# current_controller.net
KiCad netlist of a schematic drawn in EAGLE
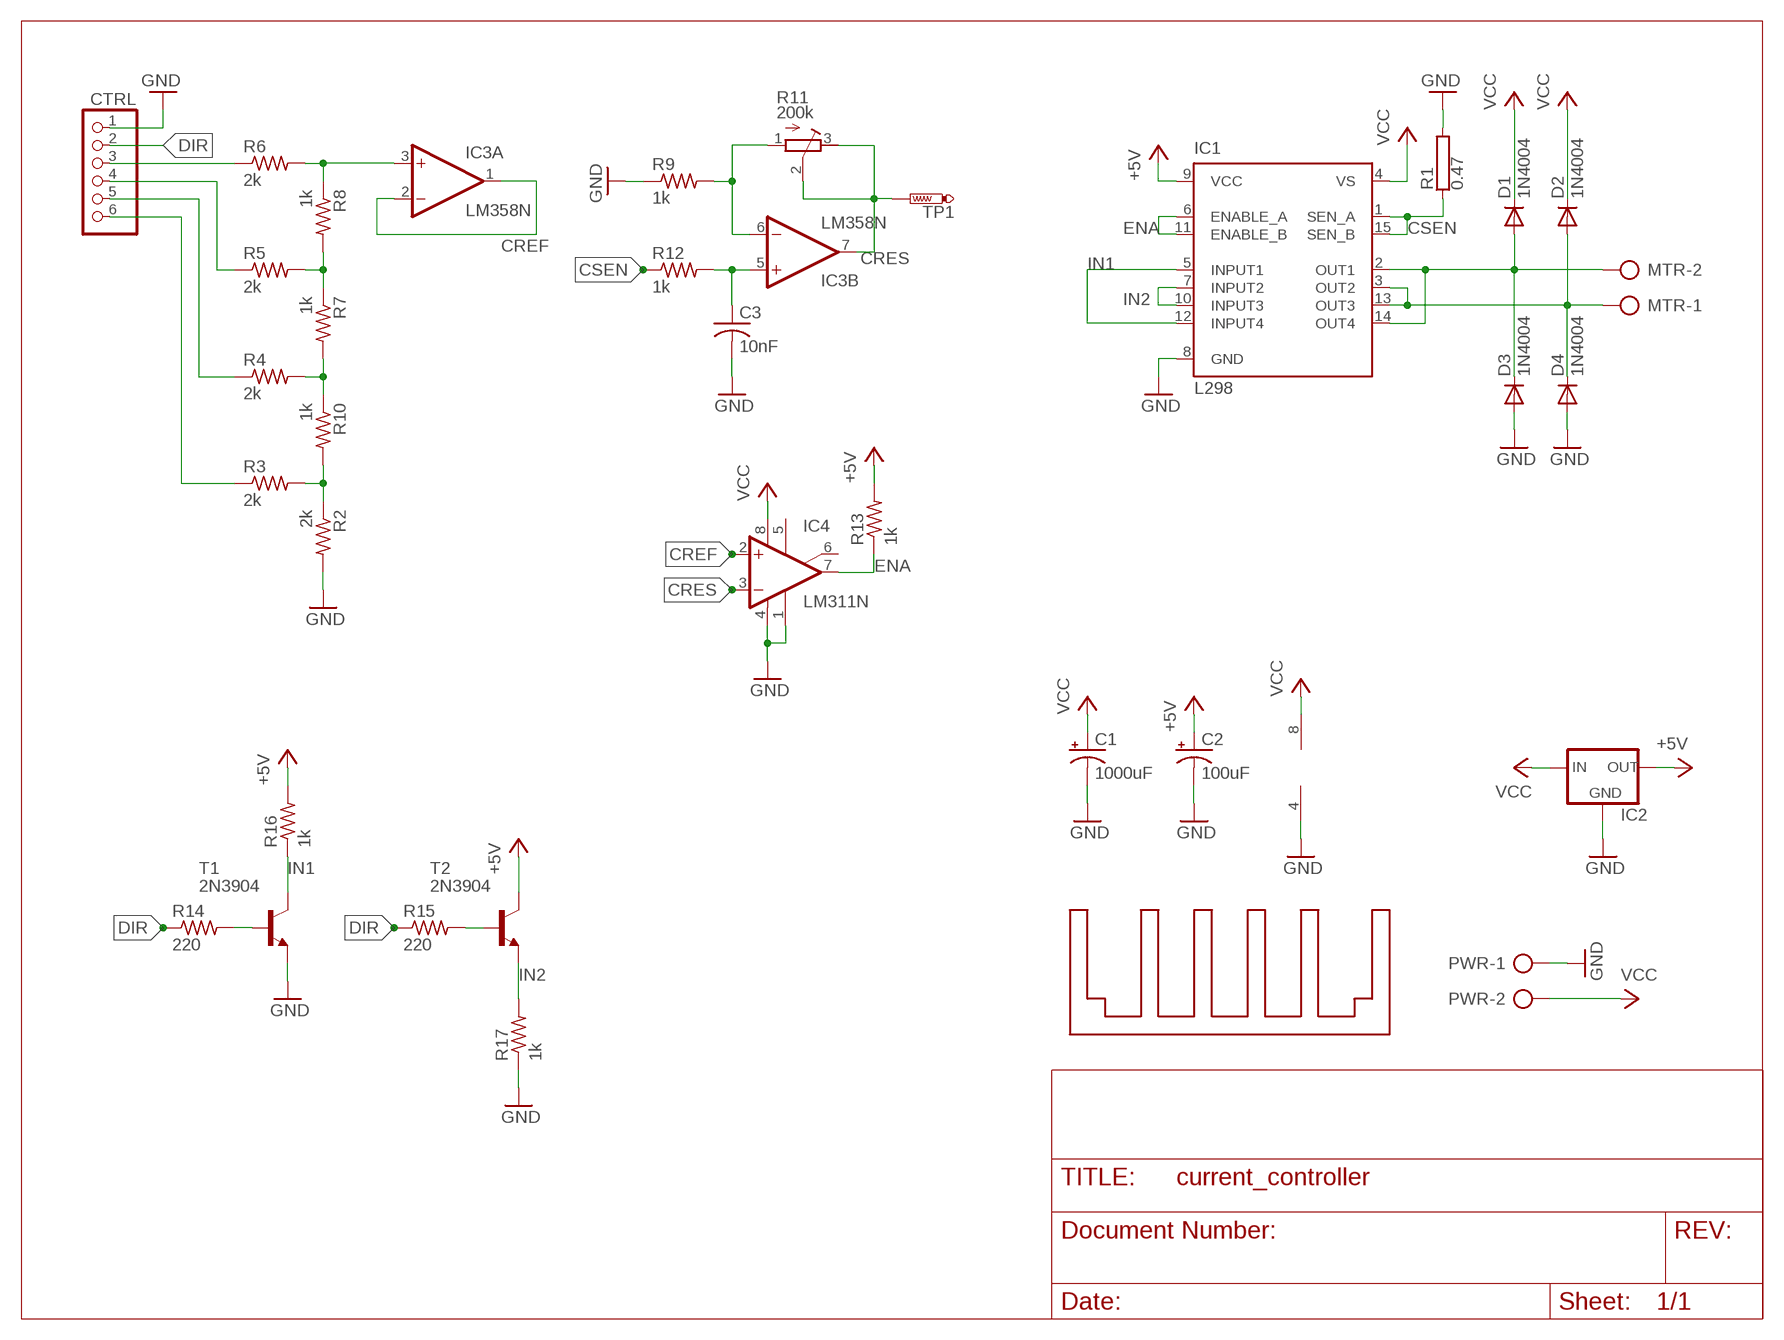
[diagram p0: schematic, sheet 1]

(export (version "E")
  (design (tool "Eeschema 10.0.6"))
  (components
    (comp (ref "C1")
      (value "1000uF")
      (footprint "eagle-import:E5-13")
      (libsource (lib "eagle-import") (part "CPOL-USE5-13"))
    )
    (comp (ref "C2")
      (value "100uF")
      (footprint "eagle-import:E5-8,5")
      (libsource (lib "eagle-import") (part "CPOL-USE5-8.5"))
    )
    (comp (ref "C3")
      (value "10nF")
      (footprint "eagle-import:C050-024X044")
      (libsource (lib "eagle-import") (part "C-US050-024X044"))
    )
    (comp (ref "CTRL")
      (value "PINHD-1X6")
      (footprint "eagle-import:1X06")
      (libsource (lib "eagle-import") (part "PINHD-1X6"))
    )
    (comp (ref "D1")
      (value "1N4004")
      (footprint "eagle-import:DO41-10")
      (libsource (lib "eagle-import") (part "1N4004"))
    )
    (comp (ref "D2")
      (value "1N4004")
      (footprint "eagle-import:DO41-10")
      (libsource (lib "eagle-import") (part "1N4004"))
    )
    (comp (ref "D3")
      (value "1N4004")
      (footprint "eagle-import:DO41-10")
      (libsource (lib "eagle-import") (part "1N4004"))
    )
    (comp (ref "D4")
      (value "1N4004")
      (footprint "eagle-import:DO41-10")
      (libsource (lib "eagle-import") (part "1N4004"))
    )
    (comp (ref "IC1")
      (value "L298")
      (footprint "eagle-import:MULTIWATT-15")
      (fields (field (name "MPN") "L298N"))
      (libsource (lib "eagle-import") (part "L298"))
    )
    (comp (ref "IC2")
      (value "78XXS")
      (footprint "eagle-import:78XXS")
      (libsource (lib "eagle-import") (part "78XXS"))
    )
    (comp (ref "IC3")
      (value "LM358N")
      (footprint "eagle-import:DIL08")
      (libsource (lib "eagle-import") (part "LM358N"))
    )
    (comp (ref "IC4")
      (value "LM311N")
      (footprint "eagle-import:DIL08")
      (libsource (lib "eagle-import") (part "LM311N"))
    )
    (comp (ref "MTR")
      (value "AK500/2")
      (footprint "eagle-import:AK500_2")
      (libsource (lib "eagle-import") (part "AK500/2"))
    )
    (comp (ref "PWR")
      (value "AK500/2")
      (footprint "eagle-import:AK500_2")
      (libsource (lib "eagle-import") (part "AK500/2"))
    )
    (comp (ref "R1")
      (value "0.47")
      (footprint "eagle-import:CA4080")
      (libsource (lib "eagle-import") (part "RCA4080"))
    )
    (comp (ref "R2")
      (value "2k")
      (footprint "eagle-import:0204_7")
      (libsource (lib "eagle-import") (part "R-US_0204/7"))
    )
    (comp (ref "R3")
      (value "2k")
      (footprint "eagle-import:0204_7")
      (libsource (lib "eagle-import") (part "R-US_0204/7"))
    )
    (comp (ref "R4")
      (value "2k")
      (footprint "eagle-import:0204_7")
      (libsource (lib "eagle-import") (part "R-US_0204/7"))
    )
    (comp (ref "R5")
      (value "2k")
      (footprint "eagle-import:0204_7")
      (libsource (lib "eagle-import") (part "R-US_0204/7"))
    )
    (comp (ref "R6")
      (value "2k")
      (footprint "eagle-import:0204_7")
      (libsource (lib "eagle-import") (part "R-US_0204/7"))
    )
    (comp (ref "R7")
      (value "1k")
      (footprint "eagle-import:0204_7")
      (libsource (lib "eagle-import") (part "R-US_0204/7"))
    )
    (comp (ref "R8")
      (value "1k")
      (footprint "eagle-import:0204_7")
      (libsource (lib "eagle-import") (part "R-US_0204/7"))
    )
    (comp (ref "R9")
      (value "1k")
      (footprint "eagle-import:0204_7")
      (libsource (lib "eagle-import") (part "R-US_0204/7"))
    )
    (comp (ref "R10")
      (value "1k")
      (footprint "eagle-import:0204_7")
      (libsource (lib "eagle-import") (part "R-US_0204/7"))
    )
    (comp (ref "R11")
      (value "200k")
      (footprint "eagle-import:RTRIM64W")
      (libsource (lib "eagle-import") (part "R-TRIMM64W"))
    )
    (comp (ref "R12")
      (value "1k")
      (footprint "eagle-import:0204_7")
      (libsource (lib "eagle-import") (part "R-US_0204/7"))
    )
    (comp (ref "R13")
      (value "1k")
      (footprint "eagle-import:0204_7")
      (libsource (lib "eagle-import") (part "R-US_0204/7"))
    )
    (comp (ref "R14")
      (value "220")
      (footprint "eagle-import:0204_7")
      (libsource (lib "eagle-import") (part "R-US_0204/7"))
    )
    (comp (ref "R15")
      (value "220")
      (footprint "eagle-import:0204_7")
      (libsource (lib "eagle-import") (part "R-US_0204/7"))
    )
    (comp (ref "R16")
      (value "1k")
      (footprint "eagle-import:0204_7")
      (libsource (lib "eagle-import") (part "R-US_0204/7"))
    )
    (comp (ref "R17")
      (value "1k")
      (footprint "eagle-import:0204_7")
      (libsource (lib "eagle-import") (part "R-US_0204/7"))
    )
    (comp (ref "T1")
      (value "2N3904")
      (footprint "eagle-import:TO92")
      (libsource (lib "eagle-import") (part "2N3904"))
    )
    (comp (ref "T2")
      (value "2N3904")
      (footprint "eagle-import:TO92")
      (libsource (lib "eagle-import") (part "2N3904"))
    )
    (comp (ref "TP1")
      (value "PTR1PAD1-13Y")
      (footprint "eagle-import:P1-13Y")
      (libsource (lib "eagle-import") (part "PTR1PAD1-13Y"))
    )
    (comp (ref "U$1")
      (value "MULTI15_HEATSINK")
      (footprint "eagle-import:MULTI15_HEATSINK")
      (libsource (lib "eagle-import") (part "MULTI15_HEATSINK"))
    )
  )
  (nets
    (net (code "1") (name "+5V") (class "Default")
      (node (ref "C2") (pin "+") (pinfunction "+_+") (pintype "passive"))
      (node (ref "IC1") (pin "9") (pinfunction "VCC_9") (pintype "power_in"))
      (node (ref "IC2") (pin "OUT") (pinfunction "OUT_OUT") (pintype "passive"))
      (node (ref "R13") (pin "2") (pinfunction "2_2") (pintype "passive"))
      (node (ref "R16") (pin "2") (pinfunction "2_2") (pintype "passive"))
      (node (ref "T2") (pin "1") (pinfunction "C_1") (pintype "passive"))
    )
    (net (code "2") (name "/ENA") (class "Default")
      (node (ref "IC1") (pin "11") (pinfunction "ENABLE_B_11") (pintype "input"))
      (node (ref "IC1") (pin "6") (pinfunction "ENABLE_A_6") (pintype "input"))
      (node (ref "IC4") (pin "7") (pinfunction "OUT_7") (pintype "output"))
      (node (ref "R13") (pin "1") (pinfunction "1_1") (pintype "passive"))
    )
    (net (code "3") (name "/IN1") (class "Default")
      (node (ref "IC1") (pin "12") (pinfunction "INPUT4_12") (pintype "input"))
      (node (ref "IC1") (pin "5") (pinfunction "INPUT1_5") (pintype "input"))
      (node (ref "R16") (pin "1") (pinfunction "1_1") (pintype "passive"))
      (node (ref "T1") (pin "1") (pinfunction "C_1") (pintype "passive"))
    )
    (net (code "4") (name "/IN2") (class "Default")
      (node (ref "IC1") (pin "10") (pinfunction "INPUT3_10") (pintype "input"))
      (node (ref "IC1") (pin "7") (pinfunction "INPUT2_7") (pintype "input"))
      (node (ref "R17") (pin "2") (pinfunction "2_2") (pintype "passive"))
      (node (ref "T2") (pin "3") (pinfunction "E_3") (pintype "passive"))
    )
    (net (code "5") (name "CREF") (class "Default")
      (node (ref "IC3") (pin "1") (pinfunction "OUT_1") (pintype "output"))
      (node (ref "IC3") (pin "2") (pinfunction "-IN_2") (pintype "input"))
      (node (ref "IC4") (pin "2") (pinfunction "+IN_2") (pintype "input"))
    )
    (net (code "6") (name "CRES") (class "Default")
      (node (ref "IC3") (pin "7") (pinfunction "OUT_7") (pintype "output"))
      (node (ref "IC4") (pin "3") (pinfunction "-IN_3") (pintype "input"))
      (node (ref "R11") (pin "2") (pinfunction "S_2") (pintype "passive"))
      (node (ref "R11") (pin "3") (pinfunction "E_3") (pintype "passive"))
      (node (ref "TP1") (pin "TP") (pinfunction "TP_TP") (pintype "input"))
    )
    (net (code "7") (name "CSEN") (class "Default")
      (node (ref "IC1") (pin "1") (pinfunction "SEN_A_1") (pintype "input"))
      (node (ref "IC1") (pin "15") (pinfunction "SEN_B_15") (pintype "input"))
      (node (ref "R1") (pin "1") (pinfunction "1_1") (pintype "passive"))
      (node (ref "R12") (pin "1") (pinfunction "1_1") (pintype "passive"))
    )
    (net (code "8") (name "DIR") (class "Default")
      (node (ref "CTRL") (pin "2") (pinfunction "2_2") (pintype "passive"))
      (node (ref "R14") (pin "1") (pinfunction "1_1") (pintype "passive"))
      (node (ref "R15") (pin "1") (pinfunction "1_1") (pintype "passive"))
    )
    (net (code "9") (name "GND") (class "Default")
      (node (ref "C1") (pin "-") (pinfunction "-_-") (pintype "passive"))
      (node (ref "C2") (pin "-") (pinfunction "-_-") (pintype "passive"))
      (node (ref "C3") (pin "2") (pinfunction "2_2") (pintype "passive"))
      (node (ref "CTRL") (pin "1") (pinfunction "1_1") (pintype "passive"))
      (node (ref "D3") (pin "A") (pinfunction "A_A") (pintype "passive"))
      (node (ref "D4") (pin "A") (pinfunction "A_A") (pintype "passive"))
      (node (ref "IC1") (pin "8") (pinfunction "GND_8") (pintype "power_in"))
      (node (ref "IC2") (pin "GND") (pinfunction "GND_GND") (pintype "input"))
      (node (ref "IC3") (pin "4") (pinfunction "V-_4") (pintype "power_in"))
      (node (ref "IC4") (pin "1") (pinfunction "GND_1") (pintype "passive"))
      (node (ref "IC4") (pin "4") (pinfunction "V-_4") (pintype "power_in"))
      (node (ref "PWR") (pin "1") (pinfunction "KL_1") (pintype "passive"))
      (node (ref "R1") (pin "2") (pinfunction "2_2") (pintype "passive"))
      (node (ref "R17") (pin "1") (pinfunction "1_1") (pintype "passive"))
      (node (ref "R2") (pin "2") (pinfunction "2_2") (pintype "passive"))
      (node (ref "R9") (pin "1") (pinfunction "1_1") (pintype "passive"))
      (node (ref "T1") (pin "3") (pinfunction "E_3") (pintype "passive"))
    )
    (net (code "10") (name "Net-(CTRL-Pad3)") (class "Default")
      (node (ref "CTRL") (pin "3") (pinfunction "3_3") (pintype "passive"))
      (node (ref "R6") (pin "1") (pinfunction "1_1") (pintype "passive"))
    )
    (net (code "11") (name "Net-(CTRL-Pad4)") (class "Default")
      (node (ref "CTRL") (pin "4") (pinfunction "4_4") (pintype "passive"))
      (node (ref "R5") (pin "1") (pinfunction "1_1") (pintype "passive"))
    )
    (net (code "12") (name "Net-(CTRL-Pad5)") (class "Default")
      (node (ref "CTRL") (pin "5") (pinfunction "5_5") (pintype "passive"))
      (node (ref "R4") (pin "1") (pinfunction "1_1") (pintype "passive"))
    )
    (net (code "13") (name "Net-(CTRL-Pad6)") (class "Default")
      (node (ref "CTRL") (pin "6") (pinfunction "6_6") (pintype "passive"))
      (node (ref "R3") (pin "1") (pinfunction "1_1") (pintype "passive"))
    )
    (net (code "14") (name "Net-(IC1-OUT1)") (class "Default")
      (node (ref "D1") (pin "A") (pinfunction "A_A") (pintype "passive"))
      (node (ref "D3") (pin "C") (pinfunction "C_C") (pintype "passive"))
      (node (ref "IC1") (pin "14") (pinfunction "OUT4_14") (pintype "output"))
      (node (ref "IC1") (pin "2") (pinfunction "OUT1_2") (pintype "output"))
      (node (ref "MTR") (pin "2") (pinfunction "KL_2") (pintype "passive"))
    )
    (net (code "15") (name "Net-(IC1-OUT2)") (class "Default")
      (node (ref "D2") (pin "A") (pinfunction "A_A") (pintype "passive"))
      (node (ref "D4") (pin "C") (pinfunction "C_C") (pintype "passive"))
      (node (ref "IC1") (pin "13") (pinfunction "OUT3_13") (pintype "output"))
      (node (ref "IC1") (pin "3") (pinfunction "OUT2_3") (pintype "output"))
      (node (ref "MTR") (pin "1") (pinfunction "KL_1") (pintype "passive"))
    )
    (net (code "16") (name "Net-(IC3A-+IN)") (class "Default")
      (node (ref "IC3") (pin "3") (pinfunction "+IN_3") (pintype "input"))
      (node (ref "R6") (pin "2") (pinfunction "2_2") (pintype "passive"))
      (node (ref "R8") (pin "1") (pinfunction "1_1") (pintype "passive"))
    )
    (net (code "17") (name "Net-(IC3B-+IN)") (class "Default")
      (node (ref "C3") (pin "1") (pinfunction "1_1") (pintype "passive"))
      (node (ref "IC3") (pin "5") (pinfunction "+IN_5") (pintype "input"))
      (node (ref "R12") (pin "2") (pinfunction "2_2") (pintype "passive"))
    )
    (net (code "18") (name "Net-(IC3B--IN)") (class "Default")
      (node (ref "IC3") (pin "6") (pinfunction "-IN_6") (pintype "input"))
      (node (ref "R11") (pin "1") (pinfunction "A_1") (pintype "passive"))
      (node (ref "R9") (pin "2") (pinfunction "2_2") (pintype "passive"))
    )
    (net (code "19") (name "Net-(R5-Pad2)") (class "Default")
      (node (ref "R5") (pin "2") (pinfunction "2_2") (pintype "passive"))
      (node (ref "R7") (pin "1") (pinfunction "1_1") (pintype "passive"))
      (node (ref "R8") (pin "2") (pinfunction "2_2") (pintype "passive"))
    )
    (net (code "20") (name "Net-(R10-Pad1)") (class "Default")
      (node (ref "R10") (pin "1") (pinfunction "1_1") (pintype "passive"))
      (node (ref "R4") (pin "2") (pinfunction "2_2") (pintype "passive"))
      (node (ref "R7") (pin "2") (pinfunction "2_2") (pintype "passive"))
    )
    (net (code "21") (name "Net-(R10-Pad2)") (class "Default")
      (node (ref "R10") (pin "2") (pinfunction "2_2") (pintype "passive"))
      (node (ref "R2") (pin "1") (pinfunction "1_1") (pintype "passive"))
      (node (ref "R3") (pin "2") (pinfunction "2_2") (pintype "passive"))
    )
    (net (code "22") (name "Net-(T1-B)") (class "Default")
      (node (ref "R14") (pin "2") (pinfunction "2_2") (pintype "passive"))
      (node (ref "T1") (pin "2") (pinfunction "B_2") (pintype "passive"))
    )
    (net (code "23") (name "Net-(T2-B)") (class "Default")
      (node (ref "R15") (pin "2") (pinfunction "2_2") (pintype "passive"))
      (node (ref "T2") (pin "2") (pinfunction "B_2") (pintype "passive"))
    )
    (net (code "24") (name "VCC") (class "Default")
      (node (ref "C1") (pin "+") (pinfunction "+_+") (pintype "passive"))
      (node (ref "D1") (pin "C") (pinfunction "C_C") (pintype "passive"))
      (node (ref "D2") (pin "C") (pinfunction "C_C") (pintype "passive"))
      (node (ref "IC1") (pin "4") (pinfunction "VS_4") (pintype "power_in"))
      (node (ref "IC2") (pin "IN") (pinfunction "IN_IN") (pintype "input"))
      (node (ref "IC3") (pin "8") (pinfunction "V+_8") (pintype "power_in"))
      (node (ref "IC4") (pin "8") (pinfunction "V+_8") (pintype "power_in"))
      (node (ref "PWR") (pin "2") (pinfunction "KL_2") (pintype "passive"))
    )
    (net (code "25") (name "unconnected-(IC4-ON-Pad5)") (class "Default")
      (node (ref "IC4") (pin "5") (pinfunction "ON_5") (pintype "passive"))
    )
    (net (code "26") (name "unconnected-(IC4-ON{slash}STR-Pad6)") (class "Default")
      (node (ref "IC4") (pin "6") (pinfunction "ON/STR_6") (pintype "passive"))
    )
  )
)
